# middlePCB_rev4.net
KiCad netlist of a schematic drawn in Altium Designer
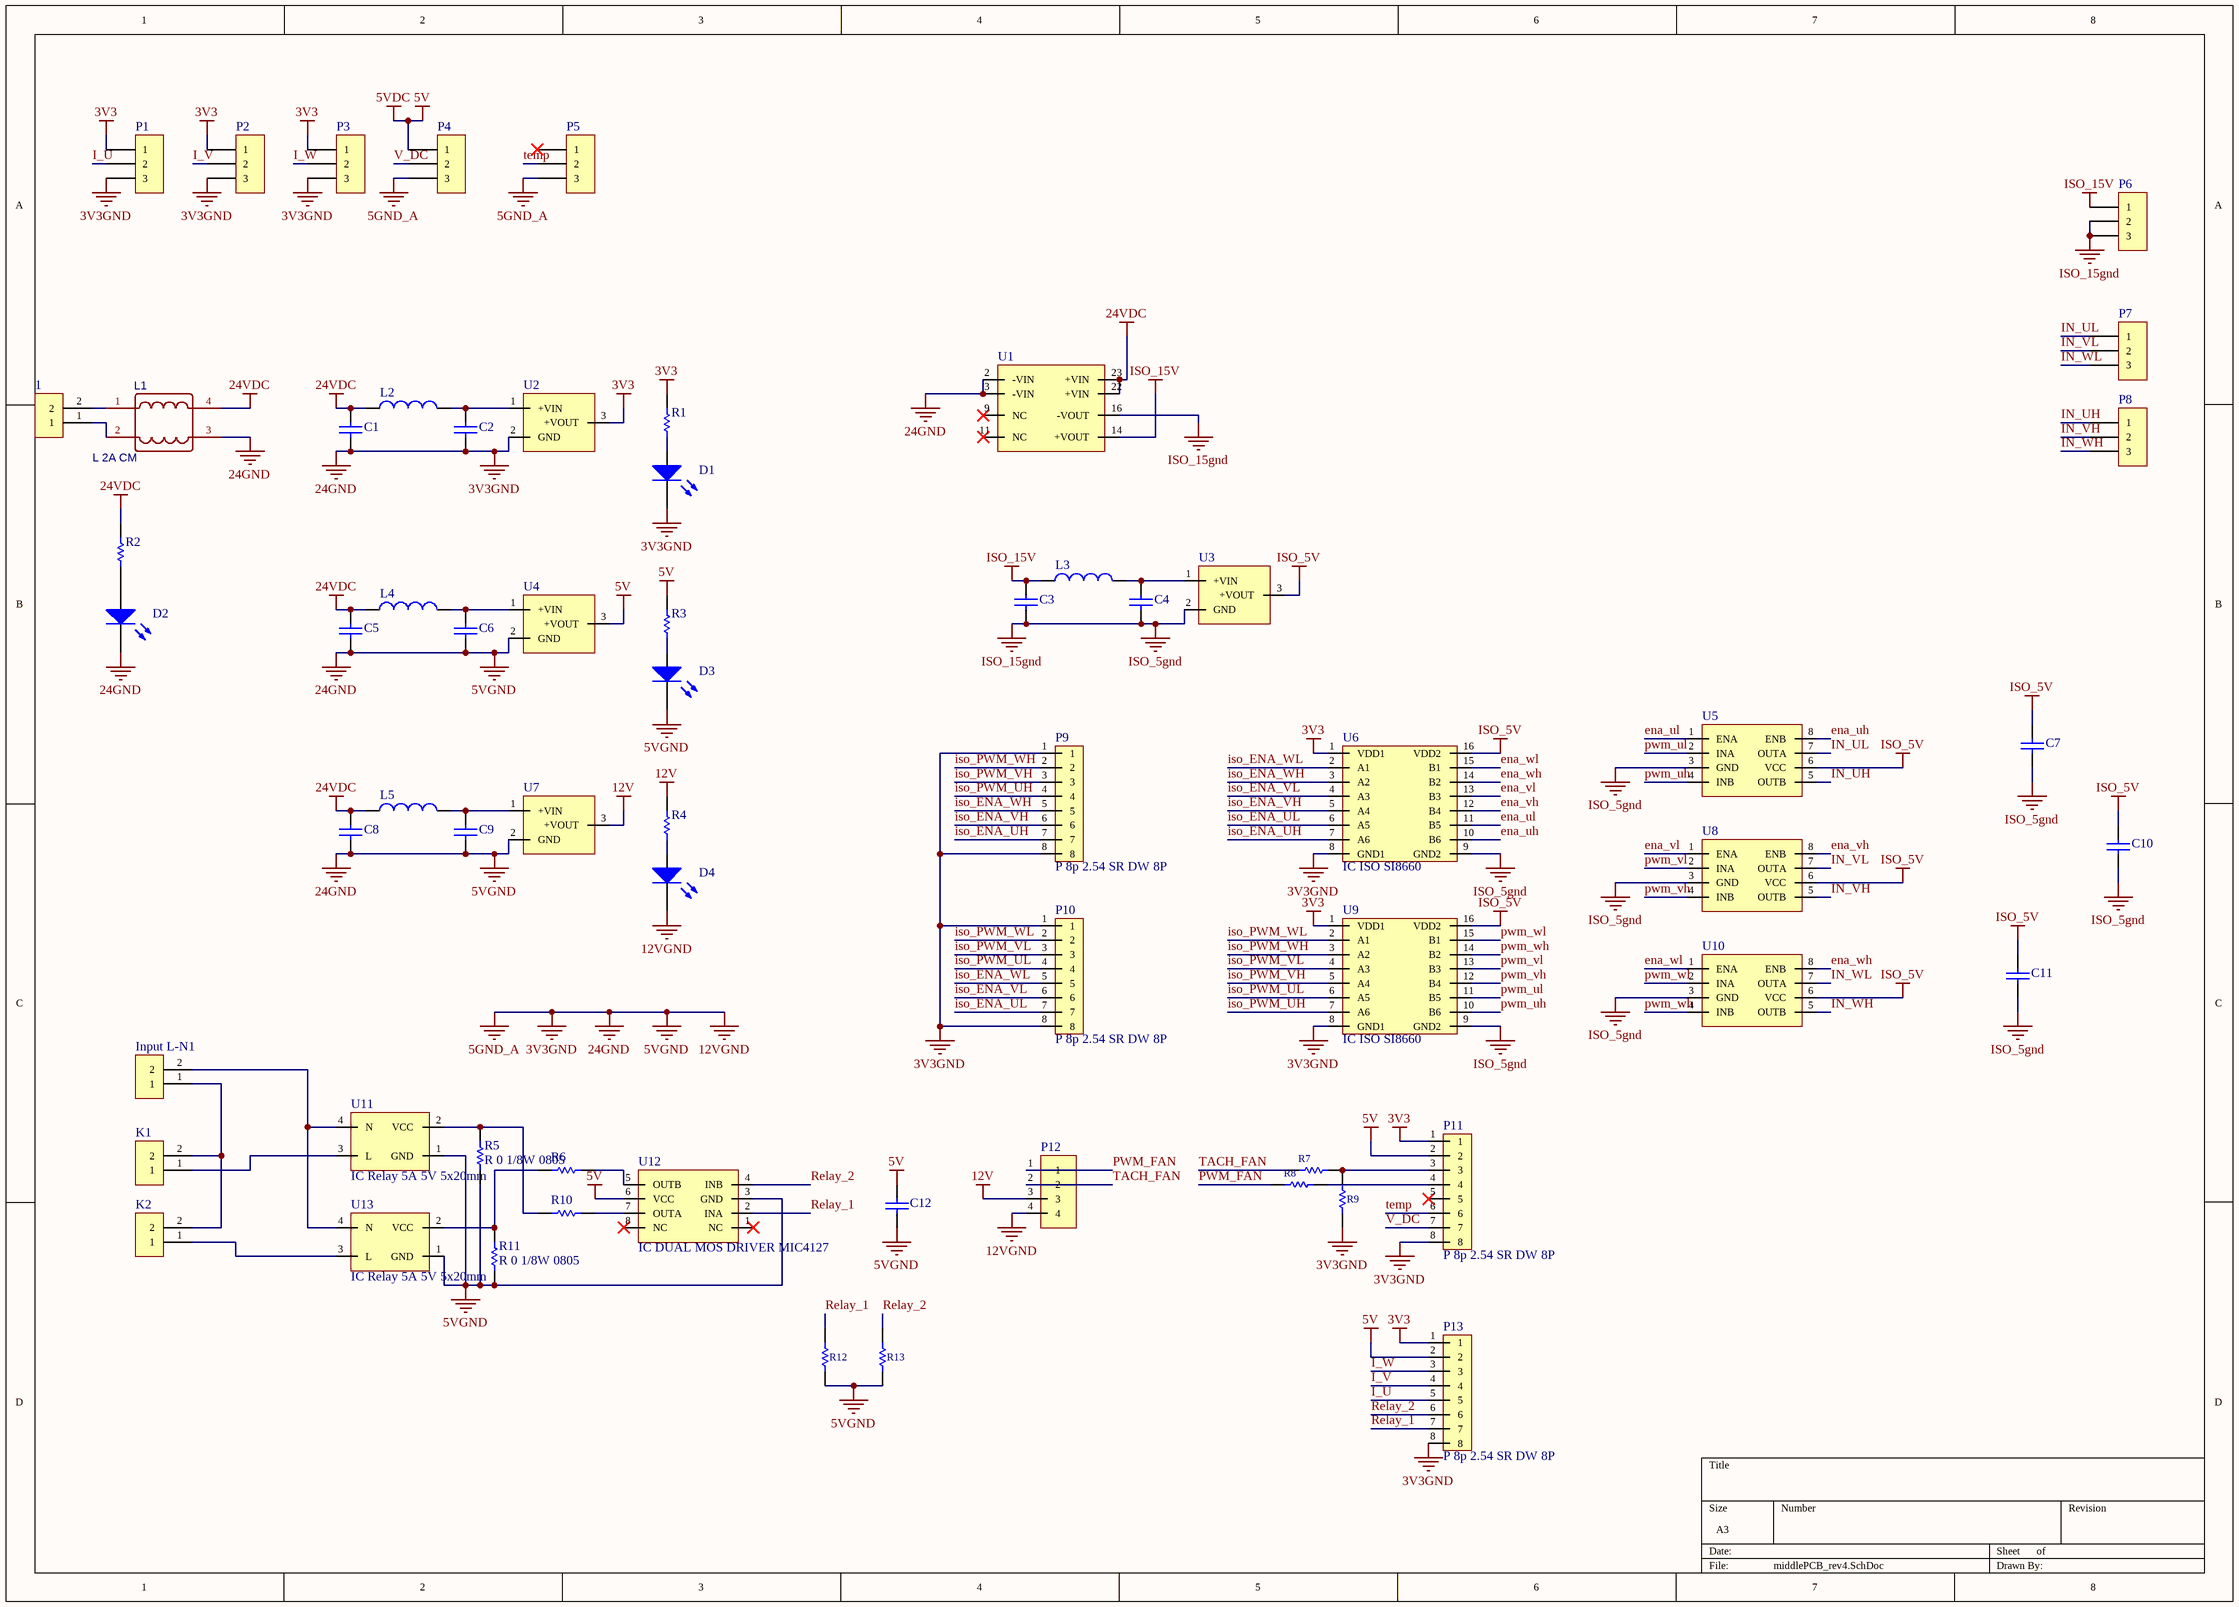
[diagram p0: middlePCB_rev4.SchDoc]

(export (version "E")
  (design (tool "Eeschema 10.0.6"))
  (components
    (comp (ref "1")
      (value "P 2p 5mm")
      (footprint "connector1x2_parafuso")
      (description "Bloques de terminales de PCB de perfil estándar RS de 5,0 mm")
      (libsource (lib "vmorais_libraries") (part "gen_purpose_conn_1x2"))
    )
    (comp (ref "C1")
      (value "C 10uF 1206 MLCC 50V X5R")
      (footprint "CAPC_1206")
      (description "Capacitores de cerâmica multicamada MLCC - SMD/SMT 1206 50V 10uF 20% X5R")
      (fields (field (name "LCSC PART #") "C13585"))
      (libsource (lib "vmorais_libraries") (part "Capacitor SMD"))
    )
    (comp (ref "C2")
      (value "C 10uF 1206 MLCC 50V X5R")
      (footprint "CAPC_1206")
      (description "Capacitores de cerâmica multicamada MLCC - SMD/SMT 1206 50V 10uF 20% X5R")
      (fields (field (name "LCSC PART #") "C13585"))
      (libsource (lib "vmorais_libraries") (part "Capacitor SMD"))
    )
    (comp (ref "C3")
      (value "C 10uF 1206 MLCC 50V X5R")
      (footprint "CAPC_1206")
      (description "Capacitores de cerâmica multicamada MLCC - SMD/SMT 1206 50V 10uF 20% X5R")
      (fields (field (name "LCSC PART #") "C13585"))
      (libsource (lib "vmorais_libraries") (part "Capacitor SMD"))
    )
    (comp (ref "C4")
      (value "C 10uF 1206 MLCC 50V X5R")
      (footprint "CAPC_1206")
      (description "Capacitores de cerâmica multicamada MLCC - SMD/SMT 1206 50V 10uF 20% X5R")
      (fields (field (name "LCSC PART #") "C13585"))
      (libsource (lib "vmorais_libraries") (part "Capacitor SMD"))
    )
    (comp (ref "C5")
      (value "C 10uF 1206 MLCC 50V X5R")
      (footprint "CAPC_1206")
      (description "Capacitores de cerâmica multicamada MLCC - SMD/SMT 1206 50V 10uF 20% X5R")
      (fields (field (name "LCSC PART #") "C13585"))
      (libsource (lib "vmorais_libraries") (part "Capacitor SMD"))
    )
    (comp (ref "C6")
      (value "C 10uF 1206 MLCC 50V X5R")
      (footprint "CAPC_1206")
      (description "Capacitores de cerâmica multicamada MLCC - SMD/SMT 1206 50V 10uF 20% X5R")
      (fields (field (name "LCSC PART #") "C13585"))
      (libsource (lib "vmorais_libraries") (part "Capacitor SMD"))
    )
    (comp (ref "C7")
      (value "C 10uF 1206 MLCC 50V X5R")
      (footprint "CAPC_1206")
      (description "Capacitores de cerâmica multicamada MLCC - SMD/SMT 1206 50V 10uF 20% X5R")
      (fields (field (name "LCSC PART #") "C13585"))
      (libsource (lib "vmorais_libraries") (part "Capacitor SMD"))
    )
    (comp (ref "C8")
      (value "C 10uF 1206 MLCC 50V X5R")
      (footprint "CAPC_1206")
      (description "Capacitores de cerâmica multicamada MLCC - SMD/SMT 1206 50V 10uF 20% X5R")
      (fields (field (name "LCSC PART #") "C13585"))
      (libsource (lib "vmorais_libraries") (part "Capacitor SMD"))
    )
    (comp (ref "C9")
      (value "C 10uF 1206 MLCC 50V X5R")
      (footprint "CAPC_1206")
      (description "Capacitores de cerâmica multicamada MLCC - SMD/SMT 1206 50V 10uF 20% X5R")
      (fields (field (name "LCSC PART #") "C13585"))
      (libsource (lib "vmorais_libraries") (part "Capacitor SMD"))
    )
    (comp (ref "C10")
      (value "C 10uF 1206 MLCC 50V X5R")
      (footprint "CAPC_1206")
      (description "Capacitores de cerâmica multicamada MLCC - SMD/SMT 1206 50V 10uF 20% X5R")
      (fields (field (name "LCSC PART #") "C13585"))
      (libsource (lib "vmorais_libraries") (part "Capacitor SMD"))
    )
    (comp (ref "C11")
      (value "C 10uF 1206 MLCC 50V X5R")
      (footprint "CAPC_1206")
      (description "Capacitores de cerâmica multicamada MLCC - SMD/SMT 1206 50V 10uF 20% X5R")
      (fields (field (name "LCSC PART #") "C13585"))
      (libsource (lib "vmorais_libraries") (part "Capacitor SMD"))
    )
    (comp (ref "C12")
      (value "C 10uF 1206 MLCC 50V X5R")
      (footprint "CAPC_1206")
      (description "Capacitores de cerâmica multicamada MLCC - SMD/SMT 1206 50V 10uF 20% X5R")
      (fields (field (name "LCSC PART #") "C13585"))
      (libsource (lib "vmorais_libraries") (part "Capacitor SMD"))
    )
    (comp (ref "D1")
      (value "IC LED 1206")
      (footprint "DIODE_1206")
      (description "LEDs padrão - SMD GREEN WATER CLEAR")
      (fields (field (name "LCSC PART #") "C88326"))
      (libsource (lib "vmorais_libraries") (part "LED"))
    )
    (comp (ref "D2")
      (value "IC LED 1206")
      (footprint "DIODE_1206")
      (description "LEDs padrão - SMD GREEN WATER CLEAR")
      (fields (field (name "LCSC PART #") "C88326"))
      (libsource (lib "vmorais_libraries") (part "LED"))
    )
    (comp (ref "D3")
      (value "IC LED 1206")
      (footprint "DIODE_1206")
      (description "LEDs padrão - SMD GREEN WATER CLEAR")
      (fields (field (name "LCSC PART #") "C88326"))
      (libsource (lib "vmorais_libraries") (part "LED"))
    )
    (comp (ref "D4")
      (value "IC LED 1206")
      (footprint "DIODE_1206")
      (description "LEDs padrão - SMD GREEN WATER CLEAR")
      (fields (field (name "LCSC PART #") "C88326"))
      (libsource (lib "vmorais_libraries") (part "LED"))
    )
    (comp (ref "Input L-N1")
      (value "P 2p 5mm")
      (footprint "connector1x2_parafuso")
      (description "Bloques de terminales de PCB de perfil estándar RS de 5,0 mm")
      (libsource (lib "vmorais_libraries") (part "gen_purpose_conn_1x2"))
    )
    (comp (ref "K1")
      (value "P 2p 5mm")
      (footprint "connector1x2_parafuso")
      (description "Bloques de terminales de PCB de perfil estándar RS de 5,0 mm")
      (libsource (lib "vmorais_libraries") (part "gen_purpose_conn_1x2"))
    )
    (comp (ref "K2")
      (value "P 2p 5mm")
      (footprint "connector1x2_parafuso")
      (description "Bloques de terminales de PCB de perfil estándar RS de 5,0 mm")
      (libsource (lib "vmorais_libraries") (part "gen_purpose_conn_1x2"))
    )
    (comp (ref "L1")
      (value "L 2A CM")
      (footprint "FILTER-SMD_4P-L9.2-W6.0-TL")
      (description "COMMON MODE CHOKES / FILTERS POWER LINE 2A SMD-4 ROHS")
      (fields (field (name "LCSC PART #") "C261397"))
      (libsource (lib "vmorais_libraries") (part "CPFC74NP-PS02H2A20"))
    )
    (comp (ref "L2")
      (value "IND RLS-126")
      (footprint "Inductor - RLS-126")
      (description "Indutores fixos Line Inductors for RECOM Power Supply")
      (libsource (lib "vmorais_libraries") (part "Inductor"))
    )
    (comp (ref "L3")
      (value "IND RLS-126")
      (footprint "Inductor - RLS-126")
      (description "Indutores fixos Line Inductors for RECOM Power Supply")
      (libsource (lib "vmorais_libraries") (part "Inductor"))
    )
    (comp (ref "L4")
      (value "IND RLS-126")
      (footprint "Inductor - RLS-126")
      (description "Indutores fixos Line Inductors for RECOM Power Supply")
      (libsource (lib "vmorais_libraries") (part "Inductor"))
    )
    (comp (ref "L5")
      (value "IND RLS-126")
      (footprint "Inductor - RLS-126")
      (description "Indutores fixos Line Inductors for RECOM Power Supply")
      (libsource (lib "vmorais_libraries") (part "Inductor"))
    )
    (comp (ref "P1")
      (value "P 8p 2.54 SR DW 3P")
      (footprint "MOLEX_3p_105431_1103")
      (description "Distribuidores e Alojamento de Fios CGrid Hrd SRDW THo le 8ckt")
      (libsource (lib "vmorais_libraries") (part "Header 3"))
    )
    (comp (ref "P2")
      (value "P 8p 2.54 SR DW 3P")
      (footprint "MOLEX_3p_105431_1103")
      (description "Distribuidores e Alojamento de Fios CGrid Hrd SRDW THo le 8ckt")
      (libsource (lib "vmorais_libraries") (part "Header 3"))
    )
    (comp (ref "P3")
      (value "P 8p 2.54 SR DW 3P")
      (footprint "MOLEX_3p_105431_1103")
      (description "Distribuidores e Alojamento de Fios CGrid Hrd SRDW THo le 8ckt")
      (libsource (lib "vmorais_libraries") (part "Header 3"))
    )
    (comp (ref "P4")
      (value "P 8p 2.54 SR DW 3P")
      (footprint "MOLEX_3p_105431_1103")
      (description "Distribuidores e Alojamento de Fios CGrid Hrd SRDW THo le 8ckt")
      (libsource (lib "vmorais_libraries") (part "Header 3"))
    )
    (comp (ref "P5")
      (value "P 8p 2.54 SR DW 3P")
      (footprint "MOLEX_3p_105431_1103")
      (description "Distribuidores e Alojamento de Fios CGrid Hrd SRDW THo le 8ckt")
      (libsource (lib "vmorais_libraries") (part "Header 3"))
    )
    (comp (ref "P6")
      (value "P 8p 2.54 SR DW 3P")
      (footprint "MOLEX_3p_105431_1103")
      (description "Distribuidores e Alojamento de Fios CGrid Hrd SRDW THo le 8ckt")
      (libsource (lib "vmorais_libraries") (part "Header 3"))
    )
    (comp (ref "P7")
      (value "P 8p 2.54 SR DW 3P")
      (footprint "MOLEX_3p_105431_1103")
      (description "Distribuidores e Alojamento de Fios CGrid Hrd SRDW THo le 8ckt")
      (libsource (lib "vmorais_libraries") (part "Header 3"))
    )
    (comp (ref "P8")
      (value "P 8p 2.54 SR DW 3P")
      (footprint "MOLEX_3p_105431_1103")
      (description "Distribuidores e Alojamento de Fios CGrid Hrd SRDW THo le 8ckt")
      (libsource (lib "vmorais_libraries") (part "Header 3"))
    )
    (comp (ref "P9")
      (value "P 8p 2.54 SR DW 8P")
      (footprint "Header 8x1 8.5mm")
      (description "Distribuidores e Alojamento de Fios CGrid Hrd SRDW THo le 8ckt")
      (libsource (lib "vmorais_libraries") (part "jumper_8p"))
    )
    (comp (ref "P10")
      (value "P 8p 2.54 SR DW 8P")
      (footprint "Header 8x1 8.5mm")
      (description "Distribuidores e Alojamento de Fios CGrid Hrd SRDW THo le 8ckt")
      (libsource (lib "vmorais_libraries") (part "jumper_8p"))
    )
    (comp (ref "P11")
      (value "P 8p 2.54 SR DW 8P")
      (footprint "Header 8x1 8.5mm")
      (description "Distribuidores e Alojamento de Fios CGrid Hrd SRDW THo le 8ckt")
      (libsource (lib "vmorais_libraries") (part "jumper_8p"))
    )
    (comp (ref "P12")
      (value "P 4p 2.54 MOL FAN")
      (footprint "HEADER 4p molex")
      (description "Distribuidores e Alojamento de Fios 4 PIN HEADER WITH FR R WITH FRICTION LOCK")
      (libsource (lib "vmorais_libraries") (part "Header 4p molex"))
    )
    (comp (ref "P13")
      (value "P 8p 2.54 SR DW 8P")
      (footprint "Header 8x1 8.5mm")
      (description "Distribuidores e Alojamento de Fios CGrid Hrd SRDW THo le 8ckt")
      (libsource (lib "vmorais_libraries") (part "jumper_8p"))
    )
    (comp (ref "R1")
      (value "R 150 1/8W 0805 1%")
      (footprint "RESC_0805")
      (description "Resistores de Filme Espesso - SMD 1/8watt 150ohms 1% 100ppm")
      (fields (field (name "LCSC PART #") "C17471"))
      (libsource (lib "vmorais_libraries") (part "Resistor"))
    )
    (comp (ref "R2")
      (value "R 2k7 1/8 0805 1%")
      (footprint "RESC_0805")
      (description "Resistores de Filme Espesso - SMD 1/8watt 2.7Kohms 1% 100ppm")
      (fields (field (name "LCSC PART #") "C17530"))
      (libsource (lib "vmorais_libraries") (part "Resistor"))
    )
    (comp (ref "R3")
      (value "R 330 1/8 0805 1%")
      (footprint "RESC_0805")
      (description "Resistores de Filme Espesso - SMD 1/8Watt 330ohms 1% Commercial Use")
      (fields (field (name "LCSC PART #") "C17630"))
      (libsource (lib "vmorais_libraries") (part "Resistor"))
    )
    (comp (ref "R4")
      (value "R 1k2 1/8 0805 1%")
      (footprint "RESC_0805")
      (description "Resistores de Filme Espesso - SMD 1/8watt 1.2Kohms 1%")
      (fields (field (name "LCSC PART #") "C17379"))
      (libsource (lib "vmorais_libraries") (part "Resistor"))
    )
    (comp (ref "R5")
      (value "R 0 1/8W 0805")
      (footprint "RESC_0805")
      (description "Resistores de Filme Espesso - SMD 1/8Watt 0ohms Commercial Use")
      (fields (field (name "LCSC PART #") "C17477"))
      (libsource (lib "vmorais_libraries") (part "Resistor"))
    )
    (comp (ref "R6")
      (value "R 10 1/8W 0805 1%")
      (footprint "RESC_0805")
      (description "Resistores de Filme Espesso - SMD 1/8Watt 10ohms 1% Commercial Use")
      (fields (field (name "LCSC PART #") "C17415"))
      (libsource (lib "vmorais_libraries") (part "Resistor"))
    )
    (comp (ref "R7")
      (value "R 0 1/8W 0805")
      (footprint "RESC_0805")
      (description "Resistores de Filme Espesso - SMD 1/8Watt 0ohms Commercial Use")
      (fields (field (name "LCSC PART #") "C17477"))
      (libsource (lib "inversor_50a") (part "Resistor"))
    )
    (comp (ref "R8")
      (value "R 0 1/8W 0805")
      (footprint "RESC_0805")
      (description "Resistores de Filme Espesso - SMD 1/8Watt 0ohms Commercial Use")
      (fields (field (name "LCSC PART #") "C17477"))
      (libsource (lib "inversor_50a") (part "Resistor"))
    )
    (comp (ref "R9")
      (value "R 0 1/8W 0805")
      (footprint "RESC_0805")
      (description "Resistores de Filme Espesso - SMD 1/8Watt 0ohms Commercial Use")
      (fields (field (name "LCSC PART #") "C17477"))
      (libsource (lib "inversor_50a") (part "Resistor"))
    )
    (comp (ref "R10")
      (value "R 10 1/8W 0805 1%")
      (footprint "RESC_0805")
      (description "Resistores de Filme Espesso - SMD 1/8Watt 10ohms 1% Commercial Use")
      (fields (field (name "LCSC PART #") "C17415"))
      (libsource (lib "vmorais_libraries") (part "Resistor"))
    )
    (comp (ref "R11")
      (value "R 0 1/8W 0805")
      (footprint "RESC_0805")
      (description "Resistores de Filme Espesso - SMD 1/8Watt 0ohms Commercial Use")
      (fields (field (name "LCSC PART #") "C17477"))
      (libsource (lib "vmorais_libraries") (part "Resistor"))
    )
    (comp (ref "R12")
      (value "R 10k 1/8W 0805")
      (footprint "RESC_0805")
      (description "Resistores de Filme Espesso - SMD 1/8Watt 0ohms Commercial Use")
      (libsource (lib "inversor_50a") (part "Resistor"))
    )
    (comp (ref "R13")
      (value "R 10k 1/8W 0805")
      (footprint "RESC_0805")
      (description "Resistores de Filme Espesso - SMD 1/8Watt 0ohms Commercial Use")
      (libsource (lib "inversor_50a") (part "Resistor"))
    )
    (comp (ref "U1")
      (value "IC DC/DC 15V ISO")
      (footprint "MeanWell SCWNo6")
      (description "Conversores CC/CC com isolação 6W 18-36Vin 15Vout 400mA DIP24 Iso")
      (libsource (lib "vmorais_libraries") (part "MEANWELL - SCWN06"))
    )
    (comp (ref "U2")
      (value "IC DC/DC 3V3")
      (footprint "DC/DC - R-78E3.3")
      (description "Conversores CC/CC sem isolação 3.3V 500MA OUT THRU")
      (libsource (lib "vmorais_libraries") (part "DC/DC - R-78E3.3"))
    )
    (comp (ref "U3")
      (value "IC DC/DC 5V")
      (footprint "DC/DC - OKI-78SR-E")
      (description "Conversores CC/CC sem isolação 7-36Vin 5Vout 1.5A VSIP Encapsulated")
      (libsource (lib "vmorais_libraries") (part "DC/DC - R-78E3.3"))
    )
    (comp (ref "U4")
      (value "IC DC/DC 5V")
      (footprint "DC/DC - OKI-78SR-E")
      (description "Conversores CC/CC sem isolação 7-36Vin 5Vout 1.5A VSIP Encapsulated")
      (libsource (lib "vmorais_libraries") (part "DC/DC - R-78E3.3"))
    )
    (comp (ref "U5")
      (value "IC Driver 5A Dual ENA IX4340")
      (footprint "SOIC-MIC4126")
      (description "Drivers de portas Dual 5A Gate Driver IC")
      (fields (field (name "LCSC PART #") "C138519"))
      (libsource (lib "vmorais_libraries") (part "Driver - IX4340"))
    )
    (comp (ref "U6")
      (value "IC ISO SI8660")
      (footprint "SOIC127P610X155-16N")
      (description "Isoladores digitais 1 kV 6-channel digital isolator")
      (libsource (lib "vmorais_libraries") (part "ISO SI8660"))
    )
    (comp (ref "U7")
      (value "IC DC/DC 12V")
      (footprint "DC/DC - OKI-78SR-E")
      (description "Conversores CC/CC sem isolação 15-36Vin 12Vout 1.0A VSIP Encapsulated")
      (libsource (lib "vmorais_libraries") (part "DC/DC - R-78E3.3"))
    )
    (comp (ref "U8")
      (value "IC Driver 5A Dual ENA IX4340")
      (footprint "SOIC-MIC4126")
      (description "Drivers de portas Dual 5A Gate Driver IC")
      (fields (field (name "LCSC PART #") "C138519"))
      (libsource (lib "vmorais_libraries") (part "Driver - IX4340"))
    )
    (comp (ref "U9")
      (value "IC ISO SI8660")
      (footprint "SOIC127P610X155-16N")
      (description "Isoladores digitais 1 kV 6-channel digital isolator")
      (libsource (lib "vmorais_libraries") (part "ISO SI8660"))
    )
    (comp (ref "U10")
      (value "IC Driver 5A Dual ENA IX4340")
      (footprint "SOIC-MIC4126")
      (description "Drivers de portas Dual 5A Gate Driver IC")
      (fields (field (name "LCSC PART #") "C138519"))
      (libsource (lib "vmorais_libraries") (part "Driver - IX4340"))
    )
    (comp (ref "U11")
      (value "IC Relay 5A 5V 5x20mm")
      (footprint "Relay - G6DN")
      (description "Relés para uso geral 1 form A w/ 5VDC Coil-standard type")
      (libsource (lib "vmorais_libraries") (part "Relay - G6DN"))
    )
    (comp (ref "U12")
      (value "IC DUAL MOS DRIVER MIC4127")
      (footprint "SOIC-MIC4126")
      (description "Drivers de portas 1.5A Dual High Speed MOSFET Driver with Low Thermal Impedance")
      (fields (field (name "LCSC PART #") "C20551"))
      (libsource (lib "vmorais_libraries") (part "MOS_DRIVER-MIC4126"))
    )
    (comp (ref "U13")
      (value "IC Relay 5A 5V 5x20mm")
      (footprint "Relay - G6DN")
      (description "Relés para uso geral 1 form A w/ 5VDC Coil-standard type")
      (libsource (lib "vmorais_libraries") (part "Relay - G6DN"))
    )
  )
  (nets
    (net (code "1") (name "/IN_UH") (class "Default")
      (node (ref "P8") (pin "1") (pinfunction "1_1") (pintype "passive"))
      (node (ref "U5") (pin "5") (pinfunction "OUTB_5") (pintype "passive"))
    )
    (net (code "2") (name "/IN_UL") (class "Default")
      (node (ref "P7") (pin "1") (pinfunction "1_1") (pintype "passive"))
      (node (ref "U5") (pin "7") (pinfunction "OUTA_7") (pintype "passive"))
    )
    (net (code "3") (name "/IN_VH") (class "Default")
      (node (ref "P8") (pin "2") (pinfunction "2_2") (pintype "passive"))
      (node (ref "U8") (pin "5") (pinfunction "OUTB_5") (pintype "passive"))
    )
    (net (code "4") (name "/IN_VL") (class "Default")
      (node (ref "P7") (pin "2") (pinfunction "2_2") (pintype "passive"))
      (node (ref "U8") (pin "7") (pinfunction "OUTA_7") (pintype "passive"))
    )
    (net (code "5") (name "/IN_WH") (class "Default")
      (node (ref "P8") (pin "3") (pinfunction "3_3") (pintype "passive"))
      (node (ref "U10") (pin "5") (pinfunction "OUTB_5") (pintype "passive"))
    )
    (net (code "6") (name "/IN_WL") (class "Default")
      (node (ref "P7") (pin "3") (pinfunction "3_3") (pintype "passive"))
      (node (ref "U10") (pin "7") (pinfunction "OUTA_7") (pintype "passive"))
    )
    (net (code "7") (name "/I_U") (class "Default")
      (node (ref "P1") (pin "2") (pinfunction "2_2") (pintype "passive"))
      (node (ref "P13") (pin "5") (pinfunction "5_5") (pintype "passive"))
    )
    (net (code "8") (name "/I_V") (class "Default")
      (node (ref "P13") (pin "4") (pinfunction "4_4") (pintype "passive"))
      (node (ref "P2") (pin "2") (pinfunction "2_2") (pintype "passive"))
    )
    (net (code "9") (name "/I_W") (class "Default")
      (node (ref "P13") (pin "3") (pinfunction "3_3") (pintype "passive"))
      (node (ref "P3") (pin "2") (pinfunction "2_2") (pintype "passive"))
    )
    (net (code "10") (name "/PWM_FAN") (class "Default")
      (node (ref "P12") (pin "1") (pinfunction "1_1") (pintype "passive"))
      (node (ref "R8") (pin "1") (pinfunction "1_1") (pintype "passive"))
    )
    (net (code "11") (name "/Relay_1") (class "Default")
      (node (ref "P13") (pin "7") (pinfunction "7_7") (pintype "passive"))
      (node (ref "R12") (pin "2") (pinfunction "2_2") (pintype "passive"))
      (node (ref "U12") (pin "2") (pinfunction "INA_2") (pintype "passive"))
    )
    (net (code "12") (name "/Relay_2") (class "Default")
      (node (ref "P13") (pin "6") (pinfunction "6_6") (pintype "passive"))
      (node (ref "R13") (pin "2") (pinfunction "2_2") (pintype "passive"))
      (node (ref "U12") (pin "4") (pinfunction "INB_4") (pintype "passive"))
    )
    (net (code "13") (name "/TACH_FAN") (class "Default")
      (node (ref "P12") (pin "2") (pinfunction "2_2") (pintype "passive"))
      (node (ref "R7") (pin "1") (pinfunction "1_1") (pintype "passive"))
    )
    (net (code "14") (name "/V_DC") (class "Default")
      (node (ref "P11") (pin "7") (pinfunction "7_7") (pintype "passive"))
      (node (ref "P4") (pin "2") (pinfunction "2_2") (pintype "passive"))
    )
    (net (code "15") (name "/ena_uh") (class "Default")
      (node (ref "U5") (pin "8") (pinfunction "ENB_8") (pintype "passive"))
      (node (ref "U6") (pin "10") (pinfunction "B6_10") (pintype "passive"))
    )
    (net (code "16") (name "/ena_ul") (class "Default")
      (node (ref "U5") (pin "1") (pinfunction "ENA_1") (pintype "passive"))
      (node (ref "U6") (pin "11") (pinfunction "B5_11") (pintype "passive"))
    )
    (net (code "17") (name "/ena_vh") (class "Default")
      (node (ref "U6") (pin "12") (pinfunction "B4_12") (pintype "passive"))
      (node (ref "U8") (pin "8") (pinfunction "ENB_8") (pintype "passive"))
    )
    (net (code "18") (name "/ena_vl") (class "Default")
      (node (ref "U6") (pin "13") (pinfunction "B3_13") (pintype "passive"))
      (node (ref "U8") (pin "1") (pinfunction "ENA_1") (pintype "passive"))
    )
    (net (code "19") (name "/ena_wh") (class "Default")
      (node (ref "U10") (pin "8") (pinfunction "ENB_8") (pintype "passive"))
      (node (ref "U6") (pin "14") (pinfunction "B2_14") (pintype "passive"))
    )
    (net (code "20") (name "/ena_wl") (class "Default")
      (node (ref "U10") (pin "1") (pinfunction "ENA_1") (pintype "passive"))
      (node (ref "U6") (pin "15") (pinfunction "B1_15") (pintype "passive"))
    )
    (net (code "21") (name "/iso_ENA_UH") (class "Default")
      (node (ref "P9") (pin "7") (pinfunction "7_7") (pintype "passive"))
      (node (ref "U6") (pin "7") (pinfunction "A6_7") (pintype "passive"))
    )
    (net (code "22") (name "/iso_ENA_UL") (class "Default")
      (node (ref "P10") (pin "7") (pinfunction "7_7") (pintype "passive"))
      (node (ref "U6") (pin "6") (pinfunction "A5_6") (pintype "passive"))
    )
    (net (code "23") (name "/iso_ENA_VH") (class "Default")
      (node (ref "P9") (pin "6") (pinfunction "6_6") (pintype "passive"))
      (node (ref "U6") (pin "5") (pinfunction "A4_5") (pintype "passive"))
    )
    (net (code "24") (name "/iso_ENA_VL") (class "Default")
      (node (ref "P10") (pin "6") (pinfunction "6_6") (pintype "passive"))
      (node (ref "U6") (pin "4") (pinfunction "A3_4") (pintype "passive"))
    )
    (net (code "25") (name "/iso_ENA_WH") (class "Default")
      (node (ref "P9") (pin "5") (pinfunction "5_5") (pintype "passive"))
      (node (ref "U6") (pin "3") (pinfunction "A2_3") (pintype "passive"))
    )
    (net (code "26") (name "/iso_ENA_WL") (class "Default")
      (node (ref "P10") (pin "5") (pinfunction "5_5") (pintype "passive"))
      (node (ref "U6") (pin "2") (pinfunction "A1_2") (pintype "passive"))
    )
    (net (code "27") (name "/iso_PWM_UH") (class "Default")
      (node (ref "P9") (pin "4") (pinfunction "4_4") (pintype "passive"))
      (node (ref "U9") (pin "7") (pinfunction "A6_7") (pintype "passive"))
    )
    (net (code "28") (name "/iso_PWM_UL") (class "Default")
      (node (ref "P10") (pin "4") (pinfunction "4_4") (pintype "passive"))
      (node (ref "U9") (pin "6") (pinfunction "A5_6") (pintype "passive"))
    )
    (net (code "29") (name "/iso_PWM_VH") (class "Default")
      (node (ref "P9") (pin "3") (pinfunction "3_3") (pintype "passive"))
      (node (ref "U9") (pin "5") (pinfunction "A4_5") (pintype "passive"))
    )
    (net (code "30") (name "/iso_PWM_VL") (class "Default")
      (node (ref "P10") (pin "3") (pinfunction "3_3") (pintype "passive"))
      (node (ref "U9") (pin "4") (pinfunction "A3_4") (pintype "passive"))
    )
    (net (code "31") (name "/iso_PWM_WH") (class "Default")
      (node (ref "P9") (pin "2") (pinfunction "2_2") (pintype "passive"))
      (node (ref "U9") (pin "3") (pinfunction "A2_3") (pintype "passive"))
    )
    (net (code "32") (name "/iso_PWM_WL") (class "Default")
      (node (ref "P10") (pin "2") (pinfunction "2_2") (pintype "passive"))
      (node (ref "U9") (pin "2") (pinfunction "A1_2") (pintype "passive"))
    )
    (net (code "33") (name "/pwm_uh") (class "Default")
      (node (ref "U5") (pin "4") (pinfunction "INB_4") (pintype "passive"))
      (node (ref "U9") (pin "10") (pinfunction "B6_10") (pintype "passive"))
    )
    (net (code "34") (name "/pwm_ul") (class "Default")
      (node (ref "U5") (pin "2") (pinfunction "INA_2") (pintype "passive"))
      (node (ref "U9") (pin "11") (pinfunction "B5_11") (pintype "passive"))
    )
    (net (code "35") (name "/pwm_vh") (class "Default")
      (node (ref "U8") (pin "4") (pinfunction "INB_4") (pintype "passive"))
      (node (ref "U9") (pin "12") (pinfunction "B4_12") (pintype "passive"))
    )
    (net (code "36") (name "/pwm_vl") (class "Default")
      (node (ref "U8") (pin "2") (pinfunction "INA_2") (pintype "passive"))
      (node (ref "U9") (pin "13") (pinfunction "B3_13") (pintype "passive"))
    )
    (net (code "37") (name "/pwm_wh") (class "Default")
      (node (ref "U10") (pin "4") (pinfunction "INB_4") (pintype "passive"))
      (node (ref "U9") (pin "14") (pinfunction "B2_14") (pintype "passive"))
    )
    (net (code "38") (name "/pwm_wl") (class "Default")
      (node (ref "U10") (pin "2") (pinfunction "INA_2") (pintype "passive"))
      (node (ref "U9") (pin "15") (pinfunction "B1_15") (pintype "passive"))
    )
    (net (code "39") (name "/temp") (class "Default")
      (node (ref "P11") (pin "6") (pinfunction "6_6") (pintype "passive"))
      (node (ref "P5") (pin "2") (pinfunction "2_2") (pintype "passive"))
    )
    (net (code "40") (name "3V3") (class "Default")
      (node (ref "P1") (pin "1") (pinfunction "1_1") (pintype "passive"))
      (node (ref "P11") (pin "1") (pinfunction "1_1") (pintype "passive"))
      (node (ref "P13") (pin "1") (pinfunction "1_1") (pintype "passive"))
      (node (ref "P2") (pin "1") (pinfunction "1_1") (pintype "passive"))
      (node (ref "P3") (pin "1") (pinfunction "1_1") (pintype "passive"))
      (node (ref "R1") (pin "2") (pinfunction "2_2") (pintype "passive"))
      (node (ref "U2") (pin "3") (pinfunction "+VOUT_3") (pintype "passive"))
      (node (ref "U6") (pin "1") (pinfunction "VDD1_1") (pintype "passive"))
      (node (ref "U9") (pin "1") (pinfunction "VDD1_1") (pintype "passive"))
    )
    (net (code "41") (name "5V") (class "Default")
      (node (ref "C12") (pin "2") (pinfunction "2_2") (pintype "passive"))
      (node (ref "P11") (pin "2") (pinfunction "2_2") (pintype "passive"))
      (node (ref "P13") (pin "2") (pinfunction "2_2") (pintype "passive"))
      (node (ref "P4") (pin "1") (pinfunction "1_1") (pintype "passive"))
      (node (ref "R3") (pin "2") (pinfunction "2_2") (pintype "passive"))
      (node (ref "U12") (pin "6") (pinfunction "VCC_6") (pintype "passive"))
      (node (ref "U4") (pin "3") (pinfunction "+VOUT_3") (pintype "passive"))
    )
    (net (code "42") (name "12V") (class "Default")
      (node (ref "P12") (pin "3") (pinfunction "3_3") (pintype "passive"))
      (node (ref "R4") (pin "2") (pinfunction "2_2") (pintype "passive"))
      (node (ref "U7") (pin "3") (pinfunction "+VOUT_3") (pintype "passive"))
    )
    (net (code "43") (name "12VGND") (class "Default")
      (node (ref "C1") (pin "1") (pinfunction "1_1") (pintype "passive"))
      (node (ref "C12") (pin "1") (pinfunction "1_1") (pintype "passive"))
      (node (ref "C2") (pin "1") (pinfunction "1_1") (pintype "passive"))
      (node (ref "C5") (pin "1") (pinfunction "1_1") (pintype "passive"))
      (node (ref "C6") (pin "1") (pinfunction "1_1") (pintype "passive"))
      (node (ref "C8") (pin "1") (pinfunction "1_1") (pintype "passive"))
      (node (ref "C9") (pin "1") (pinfunction "1_1") (pintype "passive"))
      (node (ref "D1") (pin "2") (pinfunction "K_2") (pintype "passive"))
      (node (ref "D2") (pin "2") (pinfunction "K_2") (pintype "passive"))
      (node (ref "D3") (pin "2") (pinfunction "K_2") (pintype "passive"))
      (node (ref "D4") (pin "2") (pinfunction "K_2") (pintype "passive"))
      (node (ref "L1") (pin "3") (pinfunction "3_3") (pintype "passive"))
      (node (ref "P1") (pin "3") (pinfunction "3_3") (pintype "passive"))
      (node (ref "P10") (pin "1") (pinfunction "1_1") (pintype "passive"))
      (node (ref "P10") (pin "8") (pinfunction "8_8") (pintype "passive"))
      (node (ref "P11") (pin "8") (pinfunction "8_8") (pintype "passive"))
      (node (ref "P12") (pin "4") (pinfunction "4_4") (pintype "passive"))
      (node (ref "P13") (pin "8") (pinfunction "8_8") (pintype "passive"))
      (node (ref "P2") (pin "3") (pinfunction "3_3") (pintype "passive"))
      (node (ref "P3") (pin "3") (pinfunction "3_3") (pintype "passive"))
      (node (ref "P4") (pin "3") (pinfunction "3_3") (pintype "passive"))
      (node (ref "P5") (pin "3") (pinfunction "3_3") (pintype "passive"))
      (node (ref "P9") (pin "1") (pinfunction "1_1") (pintype "passive"))
      (node (ref "P9") (pin "8") (pinfunction "8_8") (pintype "passive"))
      (node (ref "R11") (pin "2") (pinfunction "2_2") (pintype "passive"))
      (node (ref "R12") (pin "1") (pinfunction "1_1") (pintype "passive"))
      (node (ref "R13") (pin "1") (pinfunction "1_1") (pintype "passive"))
      (node (ref "R5") (pin "2") (pinfunction "2_2") (pintype "passive"))
      (node (ref "R9") (pin "1") (pinfunction "1_1") (pintype "passive"))
      (node (ref "U1") (pin "2") (pinfunction "-VIN_2") (pintype "passive"))
      (node (ref "U1") (pin "3") (pinfunction "-VIN_3") (pintype "passive"))
      (node (ref "U11") (pin "1") (pinfunction "GND_1") (pintype "passive"))
      (node (ref "U12") (pin "3") (pinfunction "GND_3") (pintype "passive"))
      (node (ref "U13") (pin "1") (pinfunction "GND_1") (pintype "passive"))
      (node (ref "U2") (pin "2") (pinfunction "GND_2") (pintype "passive"))
      (node (ref "U4") (pin "2") (pinfunction "GND_2") (pintype "passive"))
      (node (ref "U6") (pin "8") (pinfunction "GND1_8") (pintype "passive"))
      (node (ref "U7") (pin "2") (pinfunction "GND_2") (pintype "passive"))
      (node (ref "U9") (pin "8") (pinfunction "GND1_8") (pintype "passive"))
    )
    (net (code "44") (name "24VDC") (class "Default")
      (node (ref "C1") (pin "2") (pinfunction "2_2") (pintype "passive"))
      (node (ref "C5") (pin "2") (pinfunction "2_2") (pintype "passive"))
      (node (ref "C8") (pin "2") (pinfunction "2_2") (pintype "passive"))
      (node (ref "L1") (pin "4") (pinfunction "4_4") (pintype "passive"))
      (node (ref "L2") (pin "1") (pinfunction "1_1") (pintype "passive"))
      (node (ref "L4") (pin "1") (pinfunction "1_1") (pintype "passive"))
      (node (ref "L5") (pin "1") (pinfunction "1_1") (pintype "passive"))
      (node (ref "R2") (pin "2") (pinfunction "2_2") (pintype "passive"))
      (node (ref "U1") (pin "22") (pinfunction "+VIN_22") (pintype "passive"))
      (node (ref "U1") (pin "23") (pinfunction "+VIN_23") (pintype "passive"))
    )
    (net (code "45") (name "ISO_5V") (class "Default")
      (node (ref "C10") (pin "2") (pinfunction "2_2") (pintype "passive"))
      (node (ref "C11") (pin "2") (pinfunction "2_2") (pintype "passive"))
      (node (ref "C7") (pin "2") (pinfunction "2_2") (pintype "passive"))
      (node (ref "U10") (pin "6") (pinfunction "VCC_6") (pintype "passive"))
      (node (ref "U3") (pin "3") (pinfunction "+VOUT_3") (pintype "passive"))
      (node (ref "U5") (pin "6") (pinfunction "VCC_6") (pintype "passive"))
      (node (ref "U6") (pin "16") (pinfunction "VDD2_16") (pintype "passive"))
      (node (ref "U8") (pin "6") (pinfunction "VCC_6") (pintype "passive"))
      (node (ref "U9") (pin "16") (pinfunction "VDD2_16") (pintype "passive"))
    )
    (net (code "46") (name "ISO_15V") (class "Default")
      (node (ref "C3") (pin "2") (pinfunction "2_2") (pintype "passive"))
      (node (ref "L3") (pin "1") (pinfunction "1_1") (pintype "passive"))
      (node (ref "P6") (pin "1") (pinfunction "1_1") (pintype "passive"))
      (node (ref "U1") (pin "14") (pinfunction "+VOUT_14") (pintype "passive"))
    )
    (net (code "47") (name "ISO_15gnd") (class "Default")
      (node (ref "C10") (pin "1") (pinfunction "1_1") (pintype "passive"))
      (node (ref "C11") (pin "1") (pinfunction "1_1") (pintype "passive"))
      (node (ref "C3") (pin "1") (pinfunction "1_1") (pintype "passive"))
      (node (ref "C4") (pin "1") (pinfunction "1_1") (pintype "passive"))
      (node (ref "C7") (pin "1") (pinfunction "1_1") (pintype "passive"))
      (node (ref "P6") (pin "2") (pinfunction "2_2") (pintype "passive"))
      (node (ref "P6") (pin "3") (pinfunction "3_3") (pintype "passive"))
      (node (ref "U1") (pin "16") (pinfunction "-VOUT_16") (pintype "passive"))
      (node (ref "U10") (pin "3") (pinfunction "GND_3") (pintype "passive"))
      (node (ref "U3") (pin "2") (pinfunction "GND_2") (pintype "passive"))
      (node (ref "U5") (pin "3") (pinfunction "GND_3") (pintype "passive"))
      (node (ref "U6") (pin "9") (pinfunction "GND2_9") (pintype "passive"))
      (node (ref "U8") (pin "3") (pinfunction "GND_3") (pintype "passive"))
      (node (ref "U9") (pin "9") (pinfunction "GND2_9") (pintype "passive"))
    )
    (net (code "48") (name "Net-(1-Pad1)") (class "Default")
      (node (ref "1") (pin "1") (pinfunction "1_1") (pintype "passive"))
      (node (ref "L1") (pin "2") (pinfunction "2_2") (pintype "passive"))
    )
    (net (code "49") (name "Net-(1-Pad2)") (class "Default")
      (node (ref "1") (pin "2") (pinfunction "2_2") (pintype "passive"))
      (node (ref "L1") (pin "1") (pinfunction "1_1") (pintype "passive"))
    )
    (net (code "50") (name "Net-(D1-A)") (class "Default")
      (node (ref "D1") (pin "1") (pinfunction "A_1") (pintype "passive"))
      (node (ref "R1") (pin "1") (pinfunction "1_1") (pintype "passive"))
    )
    (net (code "51") (name "Net-(D2-A)") (class "Default")
      (node (ref "D2") (pin "1") (pinfunction "A_1") (pintype "passive"))
      (node (ref "R2") (pin "1") (pinfunction "1_1") (pintype "passive"))
    )
    (net (code "52") (name "Net-(D3-A)") (class "Default")
      (node (ref "D3") (pin "1") (pinfunction "A_1") (pintype "passive"))
      (node (ref "R3") (pin "1") (pinfunction "1_1") (pintype "passive"))
    )
    (net (code "53") (name "Net-(D4-A)") (class "Default")
      (node (ref "D4") (pin "1") (pinfunction "A_1") (pintype "passive"))
      (node (ref "R4") (pin "1") (pinfunction "1_1") (pintype "passive"))
    )
    (net (code "54") (name "Net-(Input L-N1-Pad1)") (class "Default")
      (node (ref "Input L-N1") (pin "1") (pinfunction "1_1") (pintype "passive"))
      (node (ref "K1") (pin "2") (pinfunction "2_2") (pintype "passive"))
      (node (ref "K2") (pin "2") (pinfunction "2_2") (pintype "passive"))
    )
    (net (code "55") (name "Net-(P11-Pad3)") (class "Default")
      (node (ref "P11") (pin "3") (pinfunction "3_3") (pintype "passive"))
      (node (ref "R7") (pin "2") (pinfunction "2_2") (pintype "passive"))
      (node (ref "R9") (pin "2") (pinfunction "2_2") (pintype "passive"))
    )
    (net (code "56") (name "Net-(P11-Pad4)") (class "Default")
      (node (ref "P11") (pin "4") (pinfunction "4_4") (pintype "passive"))
      (node (ref "R8") (pin "2") (pinfunction "2_2") (pintype "passive"))
    )
    (net (code "57") (name "Net-(U2-+VIN)") (class "Default")
      (node (ref "C2") (pin "2") (pinfunction "2_2") (pintype "passive"))
      (node (ref "L2") (pin "2") (pinfunction "2_2") (pintype "passive"))
      (node (ref "U2") (pin "1") (pinfunction "+VIN_1") (pintype "passive"))
    )
    (net (code "58") (name "Net-(U3-+VIN)") (class "Default")
      (node (ref "C4") (pin "2") (pinfunction "2_2") (pintype "passive"))
      (node (ref "L3") (pin "2") (pinfunction "2_2") (pintype "passive"))
      (node (ref "U3") (pin "1") (pinfunction "+VIN_1") (pintype "passive"))
    )
    (net (code "59") (name "Net-(U4-+VIN)") (class "Default")
      (node (ref "C6") (pin "2") (pinfunction "2_2") (pintype "passive"))
      (node (ref "L4") (pin "2") (pinfunction "2_2") (pintype "passive"))
      (node (ref "U4") (pin "1") (pinfunction "+VIN_1") (pintype "passive"))
    )
    (net (code "60") (name "Net-(U7-+VIN)") (class "Default")
      (node (ref "C9") (pin "2") (pinfunction "2_2") (pintype "passive"))
      (node (ref "L5") (pin "2") (pinfunction "2_2") (pintype "passive"))
      (node (ref "U7") (pin "1") (pinfunction "+VIN_1") (pintype "passive"))
    )
    (net (code "61") (name "Net-(U11-L)") (class "Default")
      (node (ref "K1") (pin "1") (pinfunction "1_1") (pintype "passive"))
      (node (ref "U11") (pin "3") (pinfunction "L_3") (pintype "passive"))
    )
    (net (code "62") (name "Net-(U11-N)") (class "Default")
      (node (ref "Input L-N1") (pin "2") (pinfunction "2_2") (pintype "passive"))
      (node (ref "U11") (pin "4") (pinfunction "N_4") (pintype "passive"))
      (node (ref "U13") (pin "4") (pinfunction "N_4") (pintype "passive"))
    )
    (net (code "63") (name "Net-(U11-VCC)") (class "Default")
      (node (ref "R10") (pin "2") (pinfunction "2_2") (pintype "passive"))
      (node (ref "R5") (pin "1") (pinfunction "1_1") (pintype "passive"))
      (node (ref "U11") (pin "2") (pinfunction "VCC_2") (pintype "passive"))
    )
    (net (code "64") (name "Net-(U12-OUTA)") (class "Default")
      (node (ref "R10") (pin "1") (pinfunction "1_1") (pintype "passive"))
      (node (ref "U12") (pin "7") (pinfunction "OUTA_7") (pintype "passive"))
    )
    (net (code "65") (name "Net-(U12-OUTB)") (class "Default")
      (node (ref "R6") (pin "1") (pinfunction "1_1") (pintype "passive"))
      (node (ref "U12") (pin "5") (pinfunction "OUTB_5") (pintype "passive"))
    )
    (net (code "66") (name "Net-(U13-L)") (class "Default")
      (node (ref "K2") (pin "1") (pinfunction "1_1") (pintype "passive"))
      (node (ref "U13") (pin "3") (pinfunction "L_3") (pintype "passive"))
    )
    (net (code "67") (name "Net-(U13-VCC)") (class "Default")
      (node (ref "R11") (pin "1") (pinfunction "1_1") (pintype "passive"))
      (node (ref "R6") (pin "2") (pinfunction "2_2") (pintype "passive"))
      (node (ref "U13") (pin "2") (pinfunction "VCC_2") (pintype "passive"))
    )
    (net (code "68") (name "unconnected-(P5-Pad1)") (class "Default")
      (node (ref "P5") (pin "1") (pinfunction "1_1") (pintype "passive+no_connect"))
    )
    (net (code "69") (name "unconnected-(P11-Pad5)") (class "Default")
      (node (ref "P11") (pin "5") (pinfunction "5_5") (pintype "passive+no_connect"))
    )
    (net (code "70") (name "unconnected-(U1-NC-Pad9)") (class "Default")
      (node (ref "U1") (pin "9") (pinfunction "NC_9") (pintype "passive+no_connect"))
    )
    (net (code "71") (name "unconnected-(U1-NC-Pad11)") (class "Default")
      (node (ref "U1") (pin "11") (pinfunction "NC_11") (pintype "passive+no_connect"))
    )
    (net (code "72") (name "unconnected-(U12-NC-Pad1)") (class "Default")
      (node (ref "U12") (pin "1") (pinfunction "NC_1") (pintype "passive+no_connect"))
    )
    (net (code "73") (name "unconnected-(U12-NC-Pad8)") (class "Default")
      (node (ref "U12") (pin "8") (pinfunction "NC_8") (pintype "passive+no_connect"))
    )
  )
)
